# proiect.net
KiCad netlist of a schematic drawn in EAGLE
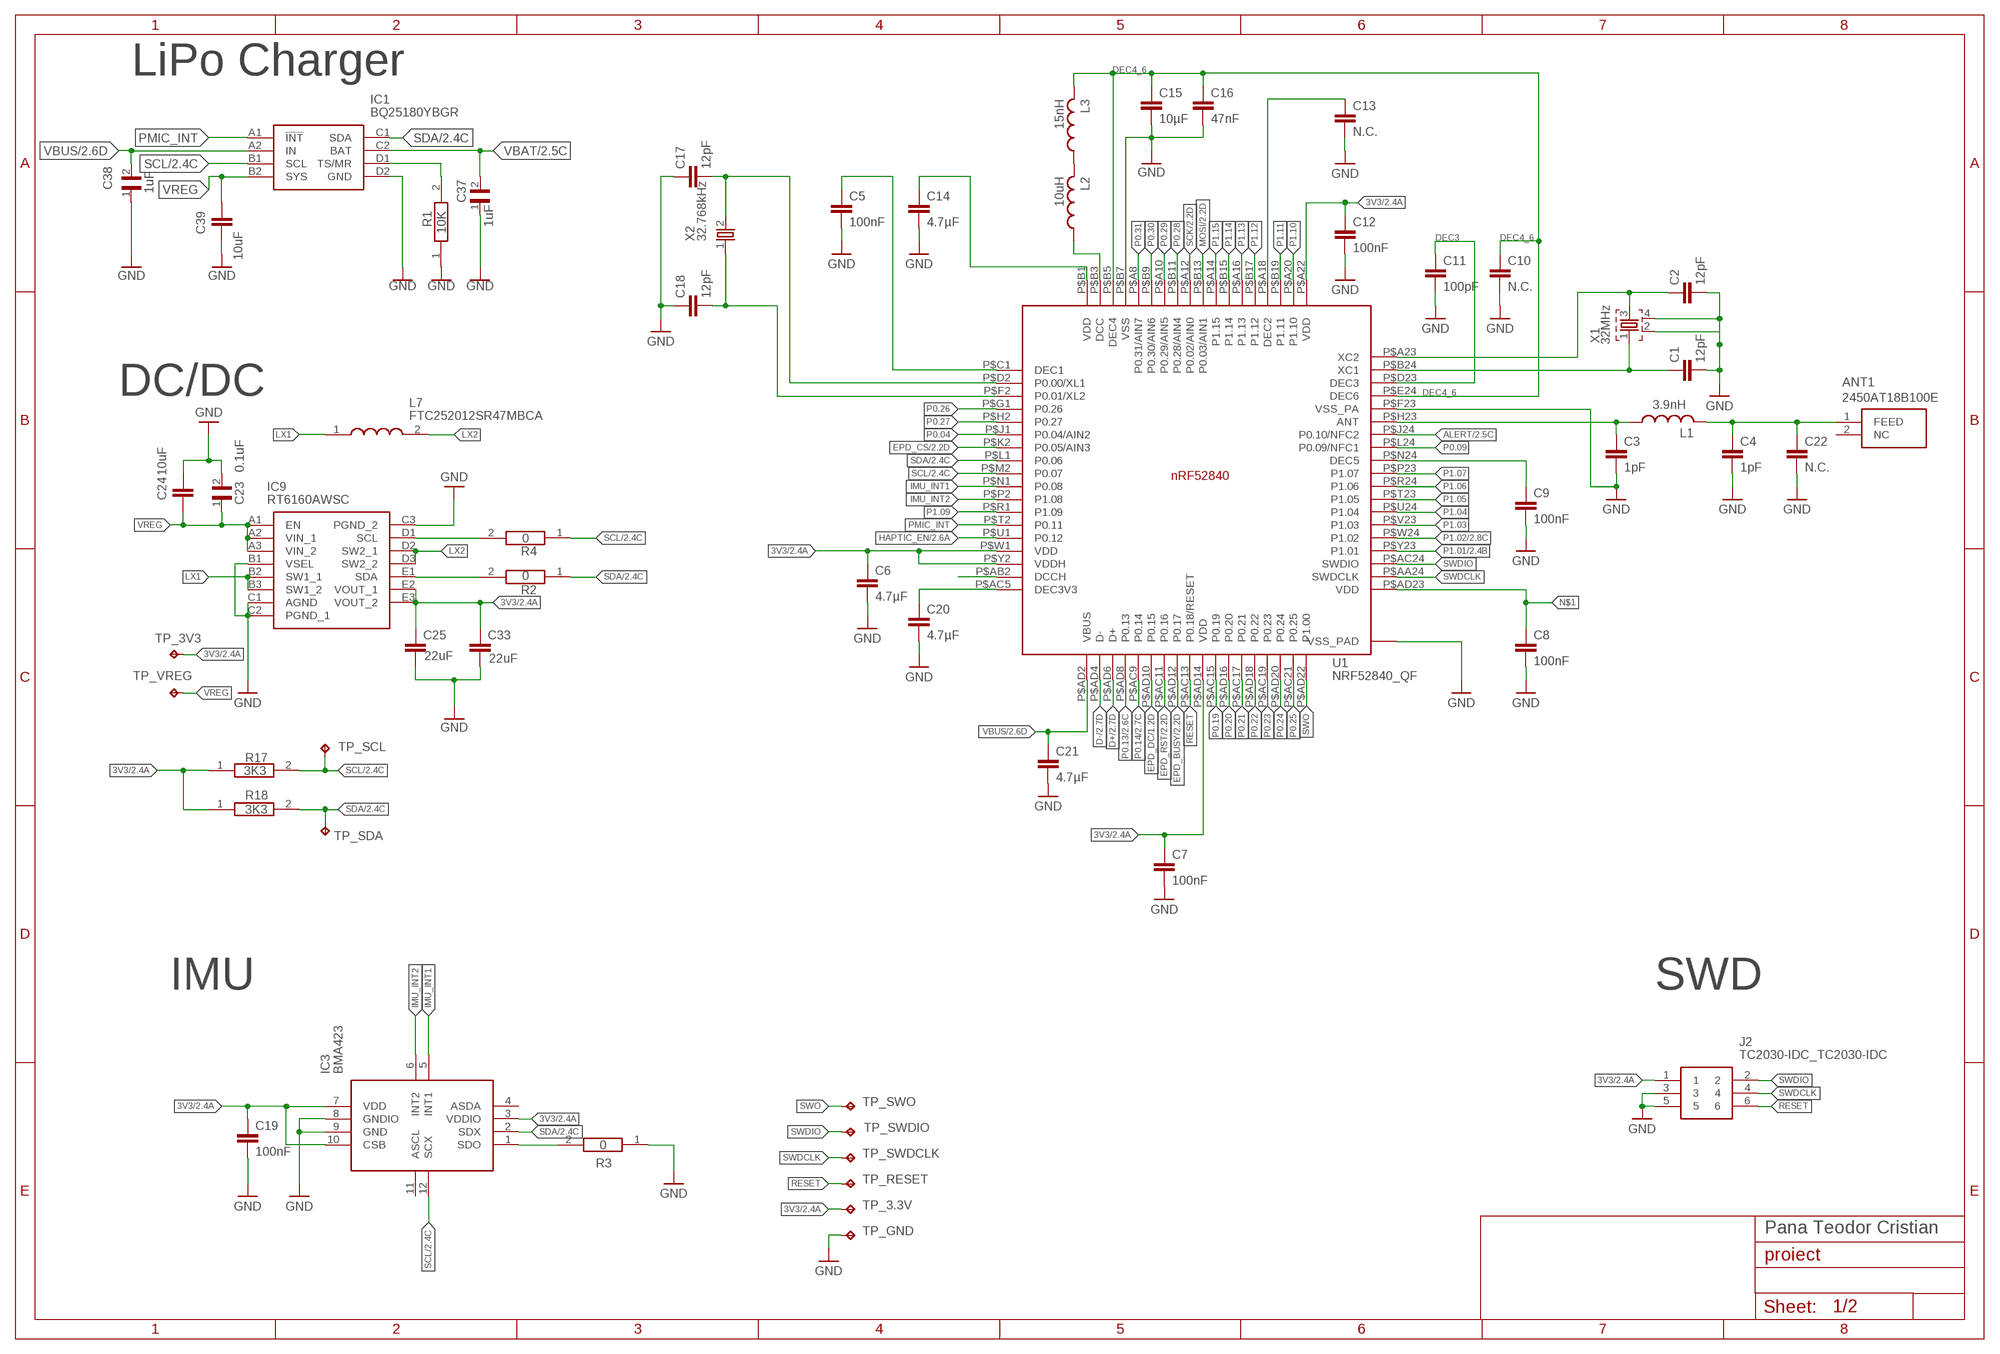
[diagram p0: schematic, sheet 1]
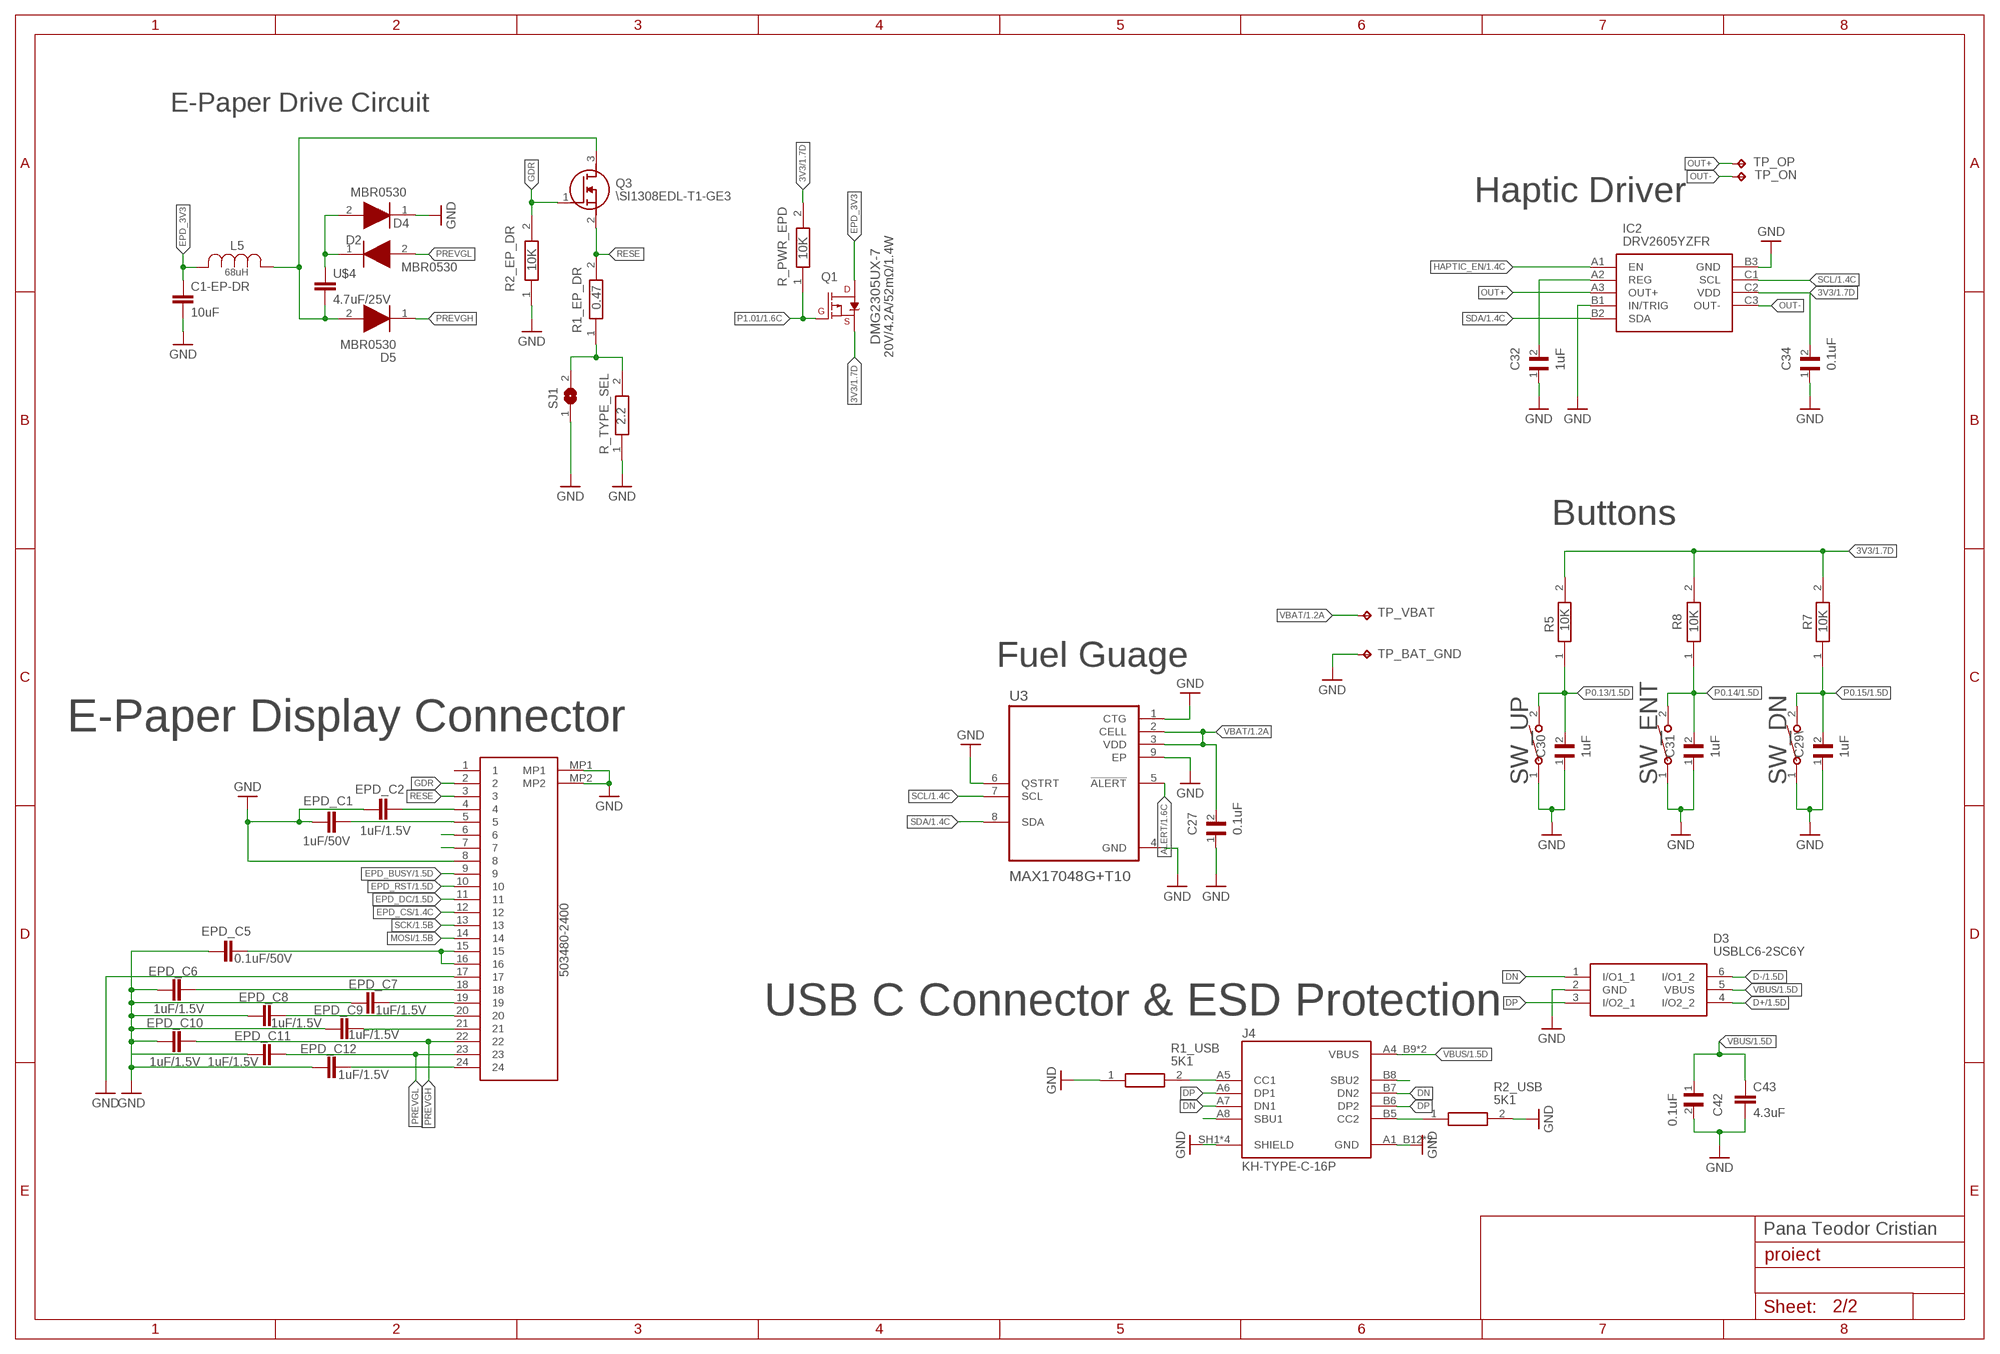
[diagram p1: schematic, sheet 2]

(export (version "E")
  (design (tool "Eeschema 10.0.6"))
  (components
    (comp (ref "C1-EP-DR")
      (value "10uF")
      (footprint "eagle-import:NORDIC_NRF_3_RESC0201_L")
      (libsource (lib "eagle-import") (part "NORDIC_NRF_3_CAPACITOR_0201_L"))
    )
    (comp (ref "C27")
      (value "0.1uF")
      (footprint "eagle-import:GRM011R60J152KE01L_2_CAPC0201X13N")
      (fields (field (name "MF") "Murata") (field (name "MP") "GRM011R60J152KE01L"))
      (libsource (lib "eagle-import") (part "GRM011R60J152KE01L_2_GRM011R60J152KE01L"))
    )
    (comp (ref "C29\\")
      (value "1uF")
      (footprint "eagle-import:GRM011R60J152KE01L_2_CAPC0201X13N")
      (fields (field (name "MF") "Murata") (field (name "MP") "GRM011R60J152KE01L"))
      (libsource (lib "eagle-import") (part "GRM011R60J152KE01L_2_GRM011R60J152KE01L"))
    )
    (comp (ref "C30")
      (value "1uF")
      (footprint "eagle-import:GRM011R60J152KE01L_2_CAPC0201X13N")
      (fields (field (name "MF") "Murata") (field (name "MP") "GRM011R60J152KE01L"))
      (libsource (lib "eagle-import") (part "GRM011R60J152KE01L_2_GRM011R60J152KE01L"))
    )
    (comp (ref "C31")
      (value "1uF")
      (footprint "eagle-import:GRM011R60J152KE01L_2_CAPC0201X13N")
      (fields (field (name "MF") "Murata") (field (name "MP") "GRM011R60J152KE01L"))
      (libsource (lib "eagle-import") (part "GRM011R60J152KE01L_2_GRM011R60J152KE01L"))
    )
    (comp (ref "C32")
      (value "1uF")
      (footprint "eagle-import:GRM011R60J152KE01L_2_CAPC0201X13N")
      (fields (field (name "MF") "Murata") (field (name "MP") "GRM011R60J152KE01L"))
      (libsource (lib "eagle-import") (part "GRM011R60J152KE01L_2_GRM011R60J152KE01L"))
    )
    (comp (ref "C34")
      (value "0.1uF")
      (footprint "eagle-import:GRM011R60J152KE01L_2_CAPC0201X13N")
      (fields (field (name "MF") "Murata") (field (name "MP") "GRM011R60J152KE01L"))
      (libsource (lib "eagle-import") (part "GRM011R60J152KE01L_2_GRM011R60J152KE01L"))
    )
    (comp (ref "C42")
      (value "0.1uF")
      (footprint "eagle-import:GRM011R60J152KE01L_2_CAPC0201X13N")
      (fields (field (name "MF") "Murata") (field (name "MP") "GRM011R60J152KE01L"))
      (libsource (lib "eagle-import") (part "GRM011R60J152KE01L_2_GRM011R60J152KE01L"))
    )
    (comp (ref "C43")
      (value "4.3uF")
      (footprint "eagle-import:NORDIC_NRF_3_RESC0201_L")
      (libsource (lib "eagle-import") (part "NORDIC_NRF_3_CAPACITOR_0201_L"))
    )
    (comp (ref "D2")
      (value "MBR0530")
      (footprint "eagle-import:ESP32_C6_LIBRARY_5_SOD3716X135N")
      (fields (field (name "MF") "ON Semiconductor"))
      (libsource (lib "eagle-import") (part "ESP32_C6_LIBRARY_5_MBR0530"))
    )
    (comp (ref "D3")
      (value "USBLC6-2SC6Y")
      (footprint "eagle-import:ESP32_C6_LIBRARY_3_SOT95P280X145-6N")
      (fields (field (name "MF") "STMicroelectronics"))
      (libsource (lib "eagle-import") (part "ESP32_C6_LIBRARY_3_USBLC6-2SC6Y"))
    )
    (comp (ref "D4")
      (value "MBR0530")
      (footprint "eagle-import:ESP32_C6_LIBRARY_5_SOD3716X135N")
      (fields (field (name "MF") "ON Semiconductor"))
      (libsource (lib "eagle-import") (part "ESP32_C6_LIBRARY_5_MBR0530"))
    )
    (comp (ref "D5")
      (value "MBR0530")
      (footprint "eagle-import:ESP32_C6_LIBRARY_5_SOD3716X135N")
      (fields (field (name "MF") "ON Semiconductor"))
      (libsource (lib "eagle-import") (part "ESP32_C6_LIBRARY_5_MBR0530"))
    )
    (comp (ref "EPD_C1")
      (value "1uF/50V")
      (footprint "eagle-import:PERFECT_0402_0402")
      (libsource (lib "eagle-import") (part "PERFECT_0402_CAP_0402"))
    )
    (comp (ref "EPD_C2")
      (value "1uF/1.5V")
      (footprint "eagle-import:PERFECT_0402_0402")
      (libsource (lib "eagle-import") (part "PERFECT_0402_CAP_0402"))
    )
    (comp (ref "EPD_C5")
      (value "0.1uF/50V")
      (footprint "eagle-import:PERFECT_0402_0402")
      (libsource (lib "eagle-import") (part "PERFECT_0402_CAP_0402"))
    )
    (comp (ref "EPD_C6")
      (value "1uF/1.5V")
      (footprint "eagle-import:PERFECT_0402_0402")
      (libsource (lib "eagle-import") (part "PERFECT_0402_CAP_0402"))
    )
    (comp (ref "EPD_C7")
      (value "1uF/1.5V")
      (footprint "eagle-import:PERFECT_0402_0402")
      (libsource (lib "eagle-import") (part "PERFECT_0402_CAP_0402"))
    )
    (comp (ref "EPD_C8")
      (value "1uF/1.5V")
      (footprint "eagle-import:PERFECT_0402_0402")
      (libsource (lib "eagle-import") (part "PERFECT_0402_CAP_0402"))
    )
    (comp (ref "EPD_C9")
      (value "1uF/1.5V")
      (footprint "eagle-import:PERFECT_0402_0402")
      (libsource (lib "eagle-import") (part "PERFECT_0402_CAP_0402"))
    )
    (comp (ref "EPD_C10")
      (value "1uF/1.5V")
      (footprint "eagle-import:PERFECT_0402_0402")
      (libsource (lib "eagle-import") (part "PERFECT_0402_CAP_0402"))
    )
    (comp (ref "EPD_C11")
      (value "1uF/1.5V")
      (footprint "eagle-import:PERFECT_0402_0402")
      (libsource (lib "eagle-import") (part "PERFECT_0402_CAP_0402"))
    )
    (comp (ref "EPD_C12")
      (value "1uF/1.5V")
      (footprint "eagle-import:PERFECT_0402_0402")
      (libsource (lib "eagle-import") (part "PERFECT_0402_CAP_0402"))
    )
    (comp (ref "IC2")
      (value "DRV2605YZFR")
      (footprint "eagle-import:DRV2605YZFR_BGA9C50P3X3_144X144X62")
      (libsource (lib "eagle-import") (part "DRV2605YZFR_DRV2605YZFR"))
    )
    (comp (ref "J1")
      (value "503480-2400")
      (footprint "eagle-import:503480-2400_5034802400")
      (fields (field (name "MOUSER_PART_NUMBER") "538-503480-2400"))
      (libsource (lib "eagle-import") (part "503480-2400_503480-2400"))
    )
    (comp (ref "J4")
      (value "KH-TYPE-C-16P")
      (footprint "eagle-import:KH-TYPE-C-16P_KINGHELM_KH-TYPE-C-16P")
      (fields (field (name "MF") "kinghelm"))
      (libsource (lib "eagle-import") (part "KH-TYPE-C-16P_KH-TYPE-C-16P"))
    )
    (comp (ref "L5")
      (value "68uH")
      (footprint "eagle-import:ESP32_C6_LIBRARY_2_IND_4828-WE-TPC_WRE")
      (fields
        (field (name "MANUFACTURER_PART_NUMBER") "744043680")
        (field (name "COPYRIGHT") "Copyright (C) 2024 Ultra Librarian. All rights reserved.")
      )
      (libsource (lib "eagle-import") (part "ESP32_C6_LIBRARY_2_744043680IND_4828-WE-TPC_WRE"))
    )
    (comp (ref "Q1")
      (value "20V/4.2A/52mΩ/1.4W")
      (footprint "eagle-import:ESP32_C6_LIBRARY_4_ESP32_C6_LIBRARY_4_ESP32_C6_LIBRARY_4_ESP32_C6_LIBRARY_4_ESP32_WROVER_SPARKFUN-DISCRETESEMI_SOT23-3")
      (libsource (lib "eagle-import") (part "ESP32_C6_LIBRARY_4_ESP32_WROVER_SPARKFUN-DISCRETESEMI_MOSFET_PCH-DMG2305UX-7"))
    )
    (comp (ref "Q3")
      (value "\\SI1308EDL-T1-GE3")
      (footprint "eagle-import:ESP32_C6_LIBRARY_6_SOT65P210X110-3N")
      (fields (field (name "MF") "Vishay Siliconix") (field (name "MP") "SI1308EDL-T1-GE3"))
      (libsource (lib "eagle-import") (part "ESP32_C6_LIBRARY_6_SI1308EDL-T1-GE3"))
    )
    (comp (ref "R1_EP_DR")
      (value "0.47")
      (footprint "eagle-import:CPF0201D7K68C1_0201")
      (libsource (lib "eagle-import") (part "CPF0201D7K68C1_CPF0201D7K68C1"))
    )
    (comp (ref "R1_USB")
      (value "5K1")
      (footprint "eagle-import:CPF0201D7K68C1_0201")
      (libsource (lib "eagle-import") (part "CPF0201D7K68C1_CPF0201D7K68C1"))
    )
    (comp (ref "R2_EP_DR")
      (value "10K")
      (footprint "eagle-import:CPF0201D7K68C1_0201")
      (libsource (lib "eagle-import") (part "CPF0201D7K68C1_CPF0201D7K68C1"))
    )
    (comp (ref "R2_USB")
      (value "5K1")
      (footprint "eagle-import:CPF0201D7K68C1_0201")
      (libsource (lib "eagle-import") (part "CPF0201D7K68C1_CPF0201D7K68C1"))
    )
    (comp (ref "R5")
      (value "10K")
      (footprint "eagle-import:CPF0201D7K68C1_0201")
      (libsource (lib "eagle-import") (part "CPF0201D7K68C1_CPF0201D7K68C1"))
    )
    (comp (ref "R7")
      (value "10K")
      (footprint "eagle-import:CPF0201D7K68C1_0201")
      (libsource (lib "eagle-import") (part "CPF0201D7K68C1_CPF0201D7K68C1"))
    )
    (comp (ref "R8")
      (value "10K")
      (footprint "eagle-import:CPF0201D7K68C1_0201")
      (libsource (lib "eagle-import") (part "CPF0201D7K68C1_CPF0201D7K68C1"))
    )
    (comp (ref "R_PWR_EPD")
      (value "10K")
      (footprint "eagle-import:CPF0201D7K68C1_0201")
      (libsource (lib "eagle-import") (part "CPF0201D7K68C1_CPF0201D7K68C1"))
    )
    (comp (ref "R_TYPE_SEL")
      (value "2.2")
      (footprint "eagle-import:CPF0201D7K68C1_0201")
      (libsource (lib "eagle-import") (part "CPF0201D7K68C1_CPF0201D7K68C1"))
    )
    (comp (ref "SJ1")
      (value "ESP32_C6_LIBRARY_7_JUMPER_SJ")
      (footprint "eagle-import:ESP32_C6_LIBRARY_7_JUMPER_SJ")
      (libsource (lib "eagle-import") (part "ESP32_C6_LIBRARY_7_JUMPER_SJ"))
    )
    (comp (ref "SW_DN")
      (value "2025-10-22_07-23-44_LIBRARY_EVP-AKE31ASW_EVP-AKE31A_PAN")
      (footprint "eagle-import:2025-10-22_07-23-44_LIBRARY_SW_EVP-AKE31A_PAN")
      (fields
        (field (name "MANUFACTURER_PART_NUMBER") "EVP-AKE31A")
        (field (name "COPYRIGHT") "Copyright (C) 2025 Ultra Librarian. All rights reserved.")
      )
      (libsource (lib "eagle-import") (part "2025-10-22_07-23-44_LIBRARY_EVP-AKE31ASW_EVP-AKE31A_PAN"))
    )
    (comp (ref "SW_ENT")
      (value "2025-10-22_07-23-44_LIBRARY_EVP-AKE31ASW_EVP-AKE31A_PAN")
      (footprint "eagle-import:2025-10-22_07-23-44_LIBRARY_SW_EVP-AKE31A_PAN")
      (fields
        (field (name "MANUFACTURER_PART_NUMBER") "EVP-AKE31A")
        (field (name "COPYRIGHT") "Copyright (C) 2025 Ultra Librarian. All rights reserved.")
      )
      (libsource (lib "eagle-import") (part "2025-10-22_07-23-44_LIBRARY_EVP-AKE31ASW_EVP-AKE31A_PAN"))
    )
    (comp (ref "SW_UP")
      (value "2025-10-22_07-23-44_LIBRARY_EVP-AKE31ASW_EVP-AKE31A_PAN")
      (footprint "eagle-import:2025-10-22_07-23-44_LIBRARY_SW_EVP-AKE31A_PAN")
      (fields
        (field (name "MANUFACTURER_PART_NUMBER") "EVP-AKE31A")
        (field (name "COPYRIGHT") "Copyright (C) 2025 Ultra Librarian. All rights reserved.")
      )
      (libsource (lib "eagle-import") (part "2025-10-22_07-23-44_LIBRARY_EVP-AKE31ASW_EVP-AKE31A_PAN"))
    )
    (comp (ref "TP_BAT_GND")
      (value "HECTOR_WATCH_1_TPTP20R")
      (footprint "eagle-import:HECTOR_WATCH_1_TP20R")
      (libsource (lib "eagle-import") (part "HECTOR_WATCH_1_TPTP20R"))
    )
    (comp (ref "TP_ON")
      (value "HECTOR_WATCH_1_TPTP20R")
      (footprint "eagle-import:HECTOR_WATCH_1_TP20R")
      (libsource (lib "eagle-import") (part "HECTOR_WATCH_1_TPTP20R"))
    )
    (comp (ref "TP_OP")
      (value "HECTOR_WATCH_1_TPTP20R")
      (footprint "eagle-import:HECTOR_WATCH_1_TP20R")
      (libsource (lib "eagle-import") (part "HECTOR_WATCH_1_TPTP20R"))
    )
    (comp (ref "TP_VBAT")
      (value "HECTOR_WATCH_1_TPTP20R")
      (footprint "eagle-import:HECTOR_WATCH_1_TP20R")
      (libsource (lib "eagle-import") (part "HECTOR_WATCH_1_TPTP20R"))
    )
    (comp (ref "U$4")
      (value "4.7uF/25V")
      (footprint "eagle-import:NORDIC_NRF_3_RESC0201_L")
      (libsource (lib "eagle-import") (part "NORDIC_NRF_3_CAPACITOR_0201_L"))
    )
    (comp (ref "U3")
      (value "MAX17048G+T10")
      (footprint "eagle-import:ESP32_C6_LIBRARY_SON50P200X200X80-9N")
      (fields (field (name "MF") "Analog Devices"))
      (libsource (lib "eagle-import") (part "ESP32_C6_LIBRARY_MAX17048G+T10"))
    )
    (comp (ref "ANT1")
      (value "2450AT18B100E")
      (footprint "eagle-import:2450AT18B100E_ANTC3216X140N")
      (fields (field (name "MOUSER_PART_NUMBER") "609-2450AT18B100E"))
      (libsource (lib "eagle-import") (part "2450AT18B100E_2450AT18B100E"))
    )
    (comp (ref "C1")
      (value "12pF")
      (footprint "eagle-import:PERFECT_0402_0402")
      (libsource (lib "eagle-import") (part "PERFECT_0402_CAP_0402"))
    )
    (comp (ref "C2")
      (value "12pF")
      (footprint "eagle-import:PERFECT_0402_0402")
      (libsource (lib "eagle-import") (part "PERFECT_0402_CAP_0402"))
    )
    (comp (ref "C3")
      (value "1pF")
      (footprint "eagle-import:NORDIC_NRF_3_RESC0201_L")
      (libsource (lib "eagle-import") (part "NORDIC_NRF_3_CAPACITOR_0201_L"))
    )
    (comp (ref "C4")
      (value "1pF")
      (footprint "eagle-import:NORDIC_NRF_3_RESC0201_L")
      (libsource (lib "eagle-import") (part "NORDIC_NRF_3_CAPACITOR_0201_L"))
    )
    (comp (ref "C5")
      (value "100nF")
      (footprint "eagle-import:NORDIC_NRF_3_RESC0201_L")
      (libsource (lib "eagle-import") (part "NORDIC_NRF_3_CAPACITOR_0201_L"))
    )
    (comp (ref "C6")
      (value "4.7µF")
      (footprint "eagle-import:PERFECT_0402_0402")
      (libsource (lib "eagle-import") (part "PERFECT_0402_CAP_0402"))
    )
    (comp (ref "C7")
      (value "100nF")
      (footprint "eagle-import:NORDIC_NRF_3_RESC0201_L")
      (libsource (lib "eagle-import") (part "NORDIC_NRF_3_CAPACITOR_0201_L"))
    )
    (comp (ref "C8")
      (value "100nF")
      (footprint "eagle-import:NORDIC_NRF_3_RESC0201_L")
      (libsource (lib "eagle-import") (part "NORDIC_NRF_3_CAPACITOR_0201_L"))
    )
    (comp (ref "C9")
      (value "100nF")
      (footprint "eagle-import:NORDIC_NRF_3_RESC0201_L")
      (libsource (lib "eagle-import") (part "NORDIC_NRF_3_CAPACITOR_0201_L"))
    )
    (comp (ref "C10")
      (value "N.C.")
      (footprint "eagle-import:PERFECT_0402_0402")
      (libsource (lib "eagle-import") (part "PERFECT_0402_CAP_0402"))
    )
    (comp (ref "C11")
      (value "100pF")
      (footprint "eagle-import:PERFECT_0402_0402")
      (libsource (lib "eagle-import") (part "PERFECT_0402_CAP_0402"))
    )
    (comp (ref "C12")
      (value "100nF")
      (footprint "eagle-import:PERFECT_0402_0402")
      (libsource (lib "eagle-import") (part "PERFECT_0402_CAP_0402"))
    )
    (comp (ref "C13")
      (value "N.C.")
      (footprint "eagle-import:PERFECT_0402_0402")
      (libsource (lib "eagle-import") (part "PERFECT_0402_CAP_0402"))
    )
    (comp (ref "C14")
      (value "4.7µF")
      (footprint "eagle-import:PERFECT_0402_0402")
      (libsource (lib "eagle-import") (part "PERFECT_0402_CAP_0402"))
    )
    (comp (ref "C15")
      (value "10µF")
      (footprint "eagle-import:PERFECT_0402_0402")
      (libsource (lib "eagle-import") (part "PERFECT_0402_CAP_0402"))
    )
    (comp (ref "C16")
      (value "47nF")
      (footprint "eagle-import:PERFECT_0402_0402")
      (libsource (lib "eagle-import") (part "PERFECT_0402_CAP_0402"))
    )
    (comp (ref "C17")
      (value "12pF")
      (footprint "eagle-import:PERFECT_0402_0402")
      (libsource (lib "eagle-import") (part "PERFECT_0402_CAP_0402"))
    )
    (comp (ref "C18")
      (value "12pF")
      (footprint "eagle-import:PERFECT_0402_0402")
      (libsource (lib "eagle-import") (part "PERFECT_0402_CAP_0402"))
    )
    (comp (ref "C19")
      (value "100nF")
      (footprint "eagle-import:PERFECT_0402_0402")
      (libsource (lib "eagle-import") (part "PERFECT_0402_CAP_0402"))
    )
    (comp (ref "C20")
      (value "4.7µF")
      (footprint "eagle-import:PERFECT_0402_0402")
      (libsource (lib "eagle-import") (part "PERFECT_0402_CAP_0402"))
    )
    (comp (ref "C21")
      (value "4.7µF")
      (footprint "eagle-import:NORDIC_NRF_3_RESC0201_L")
      (libsource (lib "eagle-import") (part "NORDIC_NRF_3_CAPACITOR_0201_L"))
    )
    (comp (ref "C22")
      (value "N.C.")
      (footprint "eagle-import:NORDIC_NRF_3_RESC0201_L")
      (libsource (lib "eagle-import") (part "NORDIC_NRF_3_CAPACITOR_0201_L"))
    )
    (comp (ref "C23")
      (value "0.1uF")
      (footprint "eagle-import:GRM011R60J152KE01L_2_CAPC0201X13N")
      (fields (field (name "MF") "Murata") (field (name "MP") "GRM011R60J152KE01L"))
      (libsource (lib "eagle-import") (part "GRM011R60J152KE01L_2_GRM011R60J152KE01L"))
    )
    (comp (ref "C24")
      (value "10uF")
      (footprint "eagle-import:PERFECT_0402_0402")
      (libsource (lib "eagle-import") (part "PERFECT_0402_CAP_0402"))
    )
    (comp (ref "C25")
      (value "22uF")
      (footprint "eagle-import:PERFECT_0402_0402")
      (libsource (lib "eagle-import") (part "PERFECT_0402_CAP_0402"))
    )
    (comp (ref "C33")
      (value "22uF")
      (footprint "eagle-import:PERFECT_0402_0402")
      (libsource (lib "eagle-import") (part "PERFECT_0402_CAP_0402"))
    )
    (comp (ref "C37")
      (value "1uF")
      (footprint "eagle-import:GRM011R60J152KE01L_2_CAPC0201X13N")
      (fields (field (name "MF") "Murata") (field (name "MP") "GRM011R60J152KE01L"))
      (libsource (lib "eagle-import") (part "GRM011R60J152KE01L_2_GRM011R60J152KE01L"))
    )
    (comp (ref "C38")
      (value "1uF")
      (footprint "eagle-import:GRM011R60J152KE01L_1_0201")
      (libsource (lib "eagle-import") (part "GRM011R60J152KE01L_1_GRM011R60J152KE01L"))
    )
    (comp (ref "C39")
      (value "10uF")
      (footprint "eagle-import:NORDIC_NRF_3_RESC0201_L")
      (libsource (lib "eagle-import") (part "NORDIC_NRF_3_CAPACITOR_0201_L"))
    )
    (comp (ref "IC1")
      (value "BQ25180YBGR")
      (footprint "eagle-import:BQ25180YBGR_BGA8C40P2X4_100X155X50")
      (fields (field (name "MOUSER_PART_NUMBER") "595-BQ25180YBGR"))
      (libsource (lib "eagle-import") (part "BQ25180YBGR_BQ25180YBGR"))
    )
    (comp (ref "IC3")
      (value "BMA423")
      (footprint "eagle-import:BMA423_BMA423")
      (fields (field (name "MOUSER_PART_NUMBER") "262-BMA423"))
      (libsource (lib "eagle-import") (part "BMA423_BMA423"))
    )
    (comp (ref "IC9")
      (value "RT6160AWSC")
      (footprint "eagle-import:RT6160AWSC_BGA15C40P3X5_140X230X60")
      (fields (field (name "MOUSER_PART_NUMBER") "835-RT6160AWSC"))
      (libsource (lib "eagle-import") (part "RT6160AWSC_RT6160AWSC"))
    )
    (comp (ref "J2")
      (value "TC2030-IDC_TC2030-IDC")
      (footprint "eagle-import:TC2030-IDC_TC2030IDC")
      (fields (field (name "MANUFACTURER_PART_NUMBER") "TC2030-IDC"))
      (libsource (lib "eagle-import") (part "TC2030-IDC_TC2030-IDC"))
    )
    (comp (ref "L1")
      (value "3.9nH")
      (footprint "eagle-import:NORDIC_NRF_2_RESC0402_L")
      (libsource (lib "eagle-import") (part "NORDIC_NRF_2_INDUCTOR_0402_L"))
    )
    (comp (ref "L2")
      (value "10uH")
      (footprint "eagle-import:NORDIC_NRF_2_RESC0402_L")
      (libsource (lib "eagle-import") (part "NORDIC_NRF_2_INDUCTOR_0402_L"))
    )
    (comp (ref "L3")
      (value "15nH")
      (footprint "eagle-import:NORDIC_NRF_2_RESC0402_L")
      (libsource (lib "eagle-import") (part "NORDIC_NRF_2_INDUCTOR_0402_L"))
    )
    (comp (ref "L7")
      (value "FTC252012SR47MBCA")
      (footprint "eagle-import:MLP2016SR47MT0S1_INDC2016X100N")
      (libsource (lib "eagle-import") (part "MLP2016SR47MT0S1_FTC252012SR47MBCA"))
    )
    (comp (ref "R1")
      (value "10K")
      (footprint "eagle-import:CPF0201D7K68C1_0201")
      (libsource (lib "eagle-import") (part "CPF0201D7K68C1_CPF0201D7K68C1"))
    )
    (comp (ref "R2")
      (value "0")
      (footprint "eagle-import:CPF0201D7K68C1_0201")
      (libsource (lib "eagle-import") (part "CPF0201D7K68C1_CPF0201D7K68C1"))
    )
    (comp (ref "R3")
      (value "0")
      (footprint "eagle-import:CPF0201D7K68C1_0201")
      (libsource (lib "eagle-import") (part "CPF0201D7K68C1_CPF0201D7K68C1"))
    )
    (comp (ref "R4")
      (value "0")
      (footprint "eagle-import:CPF0201D7K68C1_0201")
      (libsource (lib "eagle-import") (part "CPF0201D7K68C1_CPF0201D7K68C1"))
    )
    (comp (ref "R17")
      (value "3K3")
      (footprint "eagle-import:CPF0201D7K68C1_0201")
      (libsource (lib "eagle-import") (part "CPF0201D7K68C1_CPF0201D7K68C1"))
    )
    (comp (ref "R18")
      (value "3K3")
      (footprint "eagle-import:CPF0201D7K68C1_0201")
      (libsource (lib "eagle-import") (part "CPF0201D7K68C1_CPF0201D7K68C1"))
    )
    (comp (ref "TP_3.3V")
      (value "HECTOR_WATCH_1_TPTP20R")
      (footprint "eagle-import:HECTOR_WATCH_1_TP20R")
      (libsource (lib "eagle-import") (part "HECTOR_WATCH_1_TPTP20R"))
    )
    (comp (ref "TP_3V3")
      (value "HECTOR_WATCH_1_TPTP20R")
      (footprint "eagle-import:HECTOR_WATCH_1_TP20R")
      (libsource (lib "eagle-import") (part "HECTOR_WATCH_1_TPTP20R"))
    )
    (comp (ref "TP_GND")
      (value "HECTOR_WATCH_1_TPTP20R")
      (footprint "eagle-import:HECTOR_WATCH_1_TP20R")
      (libsource (lib "eagle-import") (part "HECTOR_WATCH_1_TPTP20R"))
    )
    (comp (ref "TP_RESET")
      (value "HECTOR_WATCH_1_TPTP20R")
      (footprint "eagle-import:HECTOR_WATCH_1_TP20R")
      (libsource (lib "eagle-import") (part "HECTOR_WATCH_1_TPTP20R"))
    )
    (comp (ref "TP_SCL")
      (value "HECTOR_WATCH_1_TPTP20R")
      (footprint "eagle-import:HECTOR_WATCH_1_TP20R")
      (libsource (lib "eagle-import") (part "HECTOR_WATCH_1_TPTP20R"))
    )
    (comp (ref "TP_SDA")
      (value "HECTOR_WATCH_1_TPTP20R")
      (footprint "eagle-import:HECTOR_WATCH_1_TP20R")
      (libsource (lib "eagle-import") (part "HECTOR_WATCH_1_TPTP20R"))
    )
    (comp (ref "TP_SWDCLK")
      (value "HECTOR_WATCH_1_TPTP20R")
      (footprint "eagle-import:HECTOR_WATCH_1_TP20R")
      (libsource (lib "eagle-import") (part "HECTOR_WATCH_1_TPTP20R"))
    )
    (comp (ref "TP_SWDIO")
      (value "HECTOR_WATCH_1_TPTP20R")
      (footprint "eagle-import:HECTOR_WATCH_1_TP20R")
      (libsource (lib "eagle-import") (part "HECTOR_WATCH_1_TPTP20R"))
    )
    (comp (ref "TP_SWO")
      (value "HECTOR_WATCH_1_TPTP20R")
      (footprint "eagle-import:HECTOR_WATCH_1_TP20R")
      (libsource (lib "eagle-import") (part "HECTOR_WATCH_1_TPTP20R"))
    )
    (comp (ref "TP_VREG")
      (value "HECTOR_WATCH_1_TPTP20R")
      (footprint "eagle-import:HECTOR_WATCH_1_TP20R")
      (libsource (lib "eagle-import") (part "HECTOR_WATCH_1_TPTP20R"))
    )
    (comp (ref "U1")
      (value "NRF52840_QF")
      (footprint "eagle-import:NORDIC_NRF_4_AQFN50P700X700X85_HS-74N")
      (libsource (lib "eagle-import") (part "NORDIC_NRF_4_NRF52840_QF"))
    )
    (comp (ref "X1")
      (value "32MHz")
      (footprint "eagle-import:NORDIC_NRF_BT-XTAL_2016_N")
      (libsource (lib "eagle-import") (part "NORDIC_NRF_XTAL_32MHZ"))
    )
    (comp (ref "X2")
      (value "32.768kHz")
      (footprint "eagle-import:NORDIC_NRF_1_XTAL_3215_N")
      (libsource (lib "eagle-import") (part "NORDIC_NRF_1_XTAL_32KHZ"))
    )
  )
  (nets
    (net (code "1") (name "3V3{slash}1.7D") (class "Default")
      (node (ref "C34") (pin "2") (pinfunction "2_2") (pintype "passive"))
      (node (ref "IC2") (pin "C2") (pinfunction "VDD_C2") (pintype "bidirectional"))
      (node (ref "Q1") (pin "2") (pinfunction "S_2") (pintype "bidirectional"))
      (node (ref "R5") (pin "2") (pinfunction "2_2") (pintype "bidirectional"))
      (node (ref "R7") (pin "2") (pinfunction "2_2") (pintype "bidirectional"))
      (node (ref "R8") (pin "2") (pinfunction "2_2") (pintype "bidirectional"))
      (node (ref "R_PWR_EPD") (pin "2") (pinfunction "2_2") (pintype "bidirectional"))
    )
    (net (code "2") (name "3V3{slash}2.4A") (class "Default")
      (node (ref "C12") (pin "1") (pinfunction "1_1") (pintype "passive"))
      (node (ref "C19") (pin "1") (pinfunction "1_1") (pintype "passive"))
      (node (ref "C25") (pin "1") (pinfunction "1_1") (pintype "passive"))
      (node (ref "C33") (pin "1") (pinfunction "1_1") (pintype "passive"))
      (node (ref "C6") (pin "1") (pinfunction "1_1") (pintype "passive"))
      (node (ref "C7") (pin "1") (pinfunction "1_1") (pintype "passive"))
      (node (ref "IC3") (pin "10") (pinfunction "CSB_10") (pintype "bidirectional"))
      (node (ref "IC3") (pin "3") (pinfunction "VDDIO_3") (pintype "bidirectional"))
      (node (ref "IC3") (pin "7") (pinfunction "VDD_7") (pintype "bidirectional"))
      (node (ref "IC9") (pin "E2") (pinfunction "VOUT_1_E2") (pintype "bidirectional"))
      (node (ref "IC9") (pin "E3") (pinfunction "VOUT_2_E3") (pintype "bidirectional"))
      (node (ref "J2") (pin "1") (pinfunction "1_1") (pintype "bidirectional"))
      (node (ref "R17") (pin "1") (pinfunction "1_1") (pintype "bidirectional"))
      (node (ref "R18") (pin "1") (pinfunction "1_1") (pintype "bidirectional"))
      (node (ref "TP_3.3V") (pin "TP") (pinfunction "TP_TP") (pintype "input"))
      (node (ref "TP_3V3") (pin "TP") (pinfunction "TP_TP") (pintype "input"))
      (node (ref "U1") (pin "P$A22") (pinfunction "VDD_P$A22") (pintype "power_in"))
      (node (ref "U1") (pin "P$AD14") (pinfunction "VDD_P$AD14") (pintype "power_in"))
      (node (ref "U1") (pin "P$W1") (pinfunction "VDD_P$W1") (pintype "power_in"))
      (node (ref "U1") (pin "P$Y2") (pinfunction "VDDH_P$Y2") (pintype "power_in"))
    )
    (net (code "3") (name "ALERT{slash}1.6C") (class "Default")
      (node (ref "U3") (pin "5") (pinfunction "~{ALERT}_5") (pintype "output"))
    )
    (net (code "4") (name "ALERT{slash}2.5C") (class "Default")
      (node (ref "U1") (pin "P$J24") (pinfunction "P0.10/NFC2_P$J24") (pintype "bidirectional"))
    )
    (net (code "5") (name "D+{slash}1.5D") (class "Default")
      (node (ref "D3") (pin "4") (pinfunction "I/O2_2_4") (pintype "bidirectional"))
    )
    (net (code "6") (name "D+{slash}2.7D") (class "Default")
      (node (ref "U1") (pin "P$AD6") (pinfunction "D+_P$AD6") (pintype "bidirectional"))
    )
    (net (code "7") (name "D-{slash}1.5D") (class "Default")
      (node (ref "D3") (pin "6") (pinfunction "I/O1_2_6") (pintype "bidirectional"))
    )
    (net (code "8") (name "D-{slash}2.7D") (class "Default")
      (node (ref "U1") (pin "P$AD4") (pinfunction "D-_P$AD4") (pintype "bidirectional"))
    )
    (net (code "9") (name "DN") (class "Default")
      (node (ref "D3") (pin "1") (pinfunction "I/O1_1_1") (pintype "bidirectional"))
      (node (ref "J4") (pin "A7") (pinfunction "DN1_A7") (pintype "bidirectional"))
      (node (ref "J4") (pin "B7") (pinfunction "DN2_B7") (pintype "bidirectional"))
    )
    (net (code "10") (name "DP") (class "Default")
      (node (ref "D3") (pin "3") (pinfunction "I/O2_1_3") (pintype "bidirectional"))
      (node (ref "J4") (pin "A6") (pinfunction "DP1_A6") (pintype "bidirectional"))
      (node (ref "J4") (pin "B6") (pinfunction "DP2_B6") (pintype "bidirectional"))
    )
    (net (code "11") (name "EPD_3V3") (class "Default")
      (node (ref "C1-EP-DR") (pin "1") (pinfunction "1_1") (pintype "passive"))
      (node (ref "L5") (pin "2") (pinfunction "2_2") (pintype "passive"))
      (node (ref "Q1") (pin "3") (pinfunction "D_3") (pintype "bidirectional"))
    )
    (net (code "12") (name "EPD_BUSY{slash}1.5D") (class "Default")
      (node (ref "J1") (pin "9") (pinfunction "9_9") (pintype "bidirectional"))
    )
    (net (code "13") (name "EPD_BUSY{slash}2.2D") (class "Default")
      (node (ref "U1") (pin "P$AD12") (pinfunction "P0.17_P$AD12") (pintype "bidirectional"))
    )
    (net (code "14") (name "EPD_CS{slash}1.4C") (class "Default")
      (node (ref "J1") (pin "12") (pinfunction "12_12") (pintype "bidirectional"))
    )
    (net (code "15") (name "EPD_CS{slash}2.2D") (class "Default")
      (node (ref "U1") (pin "P$K2") (pinfunction "P0.05/AIN3_P$K2") (pintype "bidirectional"))
    )
    (net (code "16") (name "EPD_DC{slash}1.2D") (class "Default")
      (node (ref "U1") (pin "P$AD10") (pinfunction "P0.15_P$AD10") (pintype "bidirectional"))
    )
    (net (code "17") (name "EPD_DC{slash}1.5D") (class "Default")
      (node (ref "J1") (pin "11") (pinfunction "11_11") (pintype "bidirectional"))
    )
    (net (code "18") (name "EPD_RST{slash}1.5D") (class "Default")
      (node (ref "J1") (pin "10") (pinfunction "10_10") (pintype "bidirectional"))
    )
    (net (code "19") (name "EPD_RST{slash}2.2D") (class "Default")
      (node (ref "U1") (pin "P$AC11") (pinfunction "P0.16_P$AC11") (pintype "bidirectional"))
    )
    (net (code "20") (name "GDR") (class "Default")
      (node (ref "J1") (pin "2") (pinfunction "2_2") (pintype "bidirectional"))
      (node (ref "Q3") (pin "1") (pinfunction "G_1") (pintype "bidirectional"))
      (node (ref "R2_EP_DR") (pin "2") (pinfunction "2_2") (pintype "bidirectional"))
    )
    (net (code "21") (name "GND") (class "Default")
      (node (ref "C1") (pin "2") (pinfunction "2_2") (pintype "passive"))
      (node (ref "C1-EP-DR") (pin "2") (pinfunction "2_2") (pintype "passive"))
      (node (ref "C10") (pin "2") (pinfunction "2_2") (pintype "passive"))
      (node (ref "C11") (pin "2") (pinfunction "2_2") (pintype "passive"))
      (node (ref "C12") (pin "2") (pinfunction "2_2") (pintype "passive"))
      (node (ref "C13") (pin "2") (pinfunction "2_2") (pintype "passive"))
      (node (ref "C14") (pin "2") (pinfunction "2_2") (pintype "passive"))
      (node (ref "C15") (pin "2") (pinfunction "2_2") (pintype "passive"))
      (node (ref "C16") (pin "2") (pinfunction "2_2") (pintype "passive"))
      (node (ref "C17") (pin "1") (pinfunction "1_1") (pintype "passive"))
      (node (ref "C18") (pin "1") (pinfunction "1_1") (pintype "passive"))
      (node (ref "C19") (pin "2") (pinfunction "2_2") (pintype "passive"))
      (node (ref "C2") (pin "2") (pinfunction "2_2") (pintype "passive"))
      (node (ref "C20") (pin "2") (pinfunction "2_2") (pintype "passive"))
      (node (ref "C21") (pin "2") (pinfunction "2_2") (pintype "passive"))
      (node (ref "C22") (pin "2") (pinfunction "2_2") (pintype "passive"))
      (node (ref "C23") (pin "2") (pinfunction "2_2") (pintype "passive"))
      (node (ref "C24") (pin "1") (pinfunction "1_1") (pintype "passive"))
      (node (ref "C25") (pin "2") (pinfunction "2_2") (pintype "passive"))
      (node (ref "C27") (pin "1") (pinfunction "1_1") (pintype "passive"))
      (node (ref "C29\\") (pin "1") (pinfunction "1_1") (pintype "passive"))
      (node (ref "C3") (pin "2") (pinfunction "2_2") (pintype "passive"))
      (node (ref "C30") (pin "1") (pinfunction "1_1") (pintype "passive"))
      (node (ref "C31") (pin "1") (pinfunction "1_1") (pintype "passive"))
      (node (ref "C32") (pin "1") (pinfunction "1_1") (pintype "passive"))
      (node (ref "C33") (pin "2") (pinfunction "2_2") (pintype "passive"))
      (node (ref "C34") (pin "1") (pinfunction "1_1") (pintype "passive"))
      (node (ref "C37") (pin "1") (pinfunction "1_1") (pintype "passive"))
      (node (ref "C38") (pin "1") (pinfunction "1_1") (pintype "passive"))
      (node (ref "C39") (pin "2") (pinfunction "2_2") (pintype "passive"))
      (node (ref "C4") (pin "2") (pinfunction "2_2") (pintype "passive"))
      (node (ref "C42") (pin "2") (pinfunction "2_2") (pintype "passive"))
      (node (ref "C43") (pin "2") (pinfunction "2_2") (pintype "passive"))
      (node (ref "C5") (pin "2") (pinfunction "2_2") (pintype "passive"))
      (node (ref "C6") (pin "2") (pinfunction "2_2") (pintype "passive"))
      (node (ref "C7") (pin "2") (pinfunction "2_2") (pintype "passive"))
      (node (ref "C8") (pin "2") (pinfunction "2_2") (pintype "passive"))
      (node (ref "C9") (pin "2") (pinfunction "2_2") (pintype "passive"))
      (node (ref "D3") (pin "2") (pinfunction "GND_2") (pintype "bidirectional"))
      (node (ref "D4") (pin "1") (pinfunction "K_1") (pintype "bidirectional"))
      (node (ref "EPD_C1") (pin "1") (pinfunction "1_1") (pintype "passive"))
      (node (ref "EPD_C10") (pin "1") (pinfunction "1_1") (pintype "passive"))
      (node (ref "EPD_C11") (pin "1") (pinfunction "1_1") (pintype "passive"))
      (node (ref "EPD_C12") (pin "1") (pinfunction "1_1") (pintype "passive"))
      (node (ref "EPD_C2") (pin "1") (pinfunction "1_1") (pintype "passive"))
      (node (ref "EPD_C5") (pin "1") (pinfunction "1_1") (pintype "passive"))
      (node (ref "EPD_C6") (pin "1") (pinfunction "1_1") (pintype "passive"))
      (node (ref "EPD_C7") (pin "1") (pinfunction "1_1") (pintype "passive"))
      (node (ref "EPD_C8") (pin "1") (pinfunction "1_1") (pintype "passive"))
      (node (ref "EPD_C9") (pin "1") (pinfunction "1_1") (pintype "passive"))
      (node (ref "IC1") (pin "D2") (pinfunction "GND_D2") (pintype "bidirectional"))
      (node (ref "IC2") (pin "B1") (pinfunction "IN/TRIG_B1") (pintype "bidirectional"))
      (node (ref "IC2") (pin "B3") (pinfunction "GND_B3") (pintype "bidirectional"))
      (node (ref "IC3") (pin "8") (pinfunction "GNDIO_8") (pintype "bidirectional"))
      (node (ref "IC3") (pin "9") (pinfunction "GND_9") (pintype "bidirectional"))
      (node (ref "IC9") (pin "B1") (pinfunction "VSEL_B1") (pintype "bidirectional"))
      (node (ref "IC9") (pin "C1") (pinfunction "AGND_C1") (pintype "bidirectional"))
      (node (ref "IC9") (pin "C2") (pinfunction "PGND_1_C2") (pintype "bidirectional"))
      (node (ref "IC9") (pin "C3") (pinfunction "PGND_2_C3") (pintype "bidirectional"))
      (node (ref "J1") (pin "17") (pinfunction "17_17") (pintype "bidirectional"))
      (node (ref "J1") (pin "8") (pinfunction "8_8") (pintype "bidirectional"))
      (node (ref "J1") (pin "MP1") (pinfunction "MP1_MP1") (pintype "bidirectional"))
      (node (ref "J1") (pin "MP2") (pinfunction "MP2_MP2") (pintype "bidirectional"))
      (node (ref "J2") (pin "3") (pinfunction "3_3") (pintype "bidirectional"))
      (node (ref "J2") (pin "5") (pinfunction "5_5") (pintype "bidirectional"))
      (node (ref "J4") (pin "A12_B1") (pinfunction "GND_A12_B1") (pintype "power_in"))
      (node (ref "J4") (pin "A1_B12") (pinfunction "GND_A1_B12") (pintype "power_in"))
      (node (ref "J4") (pin "SH1") (pinfunction "SHIELD_SH1") (pintype "passive"))
      (node (ref "J4") (pin "SH2") (pinfunction "SHIELD_SH2") (pintype "passive"))
      (node (ref "J4") (pin "SH3") (pinfunction "SHIELD_SH3") (pintype "passive"))
      (node (ref "J4") (pin "SH4") (pinfunction "SHIELD_SH4") (pintype "passive"))
      (node (ref "R1") (pin "1") (pinfunction "1_1") (pintype "bidirectional"))
      (node (ref "R1_USB") (pin "1") (pinfunction "1_1") (pintype "bidirectional"))
      (node (ref "R2_EP_DR") (pin "1") (pinfunction "1_1") (pintype "bidirectional"))
      (node (ref "R2_USB") (pin "2") (pinfunction "2_2") (pintype "bidirectional"))
      (node (ref "R3") (pin "1") (pinfunction "1_1") (pintype "bidirectional"))
      (node (ref "R_TYPE_SEL") (pin "1") (pinfunction "1_1") (pintype "bidirectional"))
      (node (ref "SJ1") (pin "1") (pinfunction "1_1") (pintype "passive"))
      (node (ref "SW_DN") (pin "1") (pinfunction "1_1") (pintype "passive"))
      (node (ref "SW_ENT") (pin "1") (pinfunction "1_1") (pintype "passive"))
      (node (ref "SW_UP") (pin "1") (pinfunction "1_1") (pintype "passive"))
      (node (ref "TP_BAT_GND") (pin "TP") (pinfunction "TP_TP") (pintype "input"))
      (node (ref "TP_GND") (pin "TP") (pinfunction "TP_TP") (pintype "input"))
      (node (ref "U1") (pin "P$74") (pinfunction "VSS_PAD_P$74") (pintype "bidirectional"))
      (node (ref "U1") (pin "P$75") (pinfunction "VSS_PAD_P$75") (pintype "bidirectional"))
      (node (ref "U1") (pin "P$76") (pinfunction "VSS_PAD_P$76") (pintype "bidirectional"))
      (node (ref "U1") (pin "P$77") (pinfunction "VSS_PAD_P$77") (pintype "bidirectional"))
      (node (ref "U1") (pin "P$78") (pinfunction "VSS_PAD_P$78") (pintype "bidirectional"))
      (node (ref "U1") (pin "P$79") (pinfunction "VSS_PAD_P$79") (pintype "bidirectional"))
      (node (ref "U1") (pin "P$80") (pinfunction "VSS_PAD_P$80") (pintype "bidirectional"))
      (node (ref "U1") (pin "P$81") (pinfunction "VSS_PAD_P$81") (pintype "bidirectional"))
      (node (ref "U1") (pin "P$82") (pinfunction "VSS_PAD_P$82") (pintype "bidirectional"))
      (node (ref "U1") (pin "P$83") (pinfunction "VSS_PAD_P$83") (pintype "bidirectional"))
      (node (ref "U1") (pin "P$84") (pinfunction "VSS_PAD_P$84") (pintype "bidirectional"))
      (node (ref "U1") (pin "P$85") (pinfunction "VSS_PAD_P$85") (pintype "bidirectional"))
      (node (ref "U1") (pin "P$86") (pinfunction "VSS_PAD_P$86") (pintype "bidirectional"))
      (node (ref "U1") (pin "P$87") (pinfunction "VSS_PAD_P$87") (pintype "bidirectional"))
      (node (ref "U1") (pin "P$88") (pinfunction "VSS_PAD_P$88") (pintype "bidirectional"))
      (node (ref "U1") (pin "P$89") (pinfunction "VSS_PAD_P$89") (pintype "bidirectional"))
      (node (ref "U1") (pin "P$90") (pinfunction "VSS_PAD_P$90") (pintype "bidirectional"))
      (node (ref "U1") (pin "P$B7") (pinfunction "VSS_P$B7") (pintype "power_in"))
      (node (ref "U1") (pin "P$F23") (pinfunction "VSS_PA_P$F23") (pintype "bidirectional"))
      (node (ref "U3") (pin "1") (pinfunction "CTG_1") (pintype "power_in"))
      (node (ref "U3") (pin "4") (pinfunction "GND_4") (pintype "power_in"))
      (node (ref "U3") (pin "6") (pinfunction "QSTRT_6") (pintype "input"))
      (node (ref "U3") (pin "9") (pinfunction "EP_9") (pintype "power_in"))
      (node (ref "X1") (pin "2") (pinfunction "2_2") (pintype "passive"))
      (node (ref "X1") (pin "4") (pinfunction "4_4") (pintype "passive"))
    )
    (net (code "22") (name "HAPTIC_EN{slash}1.4C") (class "Default")
      (node (ref "IC2") (pin "A1") (pinfunction "EN_A1") (pintype "bidirectional"))
    )
    (net (code "23") (name "HAPTIC_EN{slash}2.6A") (class "Default")
      (node (ref "U1") (pin "P$U1") (pinfunction "P0.12_P$U1") (pintype "bidirectional"))
    )
    (net (code "24") (name "IMU_INT1") (class "Default")
      (node (ref "IC3") (pin "5") (pinfunction "INT1_5") (pintype "bidirectional"))
      (node (ref "U1") (pin "P$N1") (pinfunction "P0.08_P$N1") (pintype "bidirectional"))
    )
    (net (code "25") (name "IMU_INT2") (class "Default")
      (node (ref "IC3") (pin "6") (pinfunction "INT2_6") (pintype "bidirectional"))
      (node (ref "U1") (pin "P$P2") (pinfunction "P1.08_P$P2") (pintype "bidirectional"))
    )
    (net (code "26") (name "LX1") (class "Default")
      (node (ref "IC9") (pin "B2") (pinfunction "SW1_1_B2") (pintype "bidirectional"))
      (node (ref "IC9") (pin "B3") (pinfunction "SW1_2_B3") (pintype "bidirectional"))
      (node (ref "L7") (pin "1") (pinfunction "1_1") (pintype "bidirectional"))
    )
    (net (code "27") (name "LX2") (class "Default")
      (node (ref "IC9") (pin "D2") (pinfunction "SW2_1_D2") (pintype "bidirectional"))
      (node (ref "IC9") (pin "D3") (pinfunction "SW2_2_D3") (pintype "bidirectional"))
      (node (ref "L7") (pin "2") (pinfunction "2_2") (pintype "bidirectional"))
    )
    (net (code "28") (name "MOSI{slash}1.5B") (class "Default")
      (node (ref "J1") (pin "14") (pinfunction "14_14") (pintype "bidirectional"))
    )
    (net (code "29") (name "MOSI{slash}2.2D") (class "Default")
      (node (ref "U1") (pin "P$B13") (pinfunction "P0.03/AIN1_P$B13") (pintype "bidirectional"))
    )
    (net (code "30") (name "N$1") (class "Default")
      (node (ref "C8") (pin "1") (pinfunction "1_1") (pintype "passive"))
      (node (ref "U1") (pin "P$AD23") (pinfunction "VDD_P$AD23") (pintype "power_in"))
    )
    (net (code "31") (name "Net-(ANT1-FEED)") (class "Default")
      (node (ref "ANT1") (pin "1") (pinfunction "FEED_1") (pintype "input"))
      (node (ref "C22") (pin "1") (pinfunction "1_1") (pintype "passive"))
      (node (ref "C4") (pin "1") (pinfunction "1_1") (pintype "passive"))
      (node (ref "L1") (pin "2") (pinfunction "2_2") (pintype "passive"))
    )
    (net (code "32") (name "Net-(C14-Pad1)") (class "Default")
      (node (ref "C14") (pin "1") (pinfunction "1_1") (pintype "passive"))
      (node (ref "U1") (pin "P$B1") (pinfunction "VDD_P$B1") (pintype "power_in"))
    )
    (net (code "33") (name "Net-(D2-K)") (class "Default")
      (node (ref "D2") (pin "1") (pinfunction "K_1") (pintype "bidirectional"))
      (node (ref "D4") (pin "2") (pinfunction "A_2") (pintype "bidirectional"))
      (node (ref "U$4") (pin "1") (pinfunction "1_1") (pintype "passive"))
    )
    (net (code "34") (name "Net-(D5-A)") (class "Default")
      (node (ref "D5") (pin "2") (pinfunction "A_2") (pintype "bidirectional"))
      (node (ref "L5") (pin "1") (pinfunction "1_1") (pintype "passive"))
      (node (ref "Q3") (pin "3") (pinfunction "D_3") (pintype "bidirectional"))
      (node (ref "U$4") (pin "2") (pinfunction "2_2") (pintype "passive"))
    )
    (net (code "35") (name "Net-(EPD_C1-Pad2)") (class "Default")
      (node (ref "EPD_C1") (pin "2") (pinfunction "2_2") (pintype "passive"))
      (node (ref "J1") (pin "5") (pinfunction "5_5") (pintype "bidirectional"))
    )
    (net (code "36") (name "Net-(EPD_C2-Pad2)") (class "Default")
      (node (ref "EPD_C2") (pin "2") (pinfunction "2_2") (pintype "passive"))
      (node (ref "J1") (pin "4") (pinfunction "4_4") (pintype "bidirectional"))
    )
    (net (code "37") (name "Net-(EPD_C5-Pad2)") (class "Default")
      (node (ref "EPD_C5") (pin "2") (pinfunction "2_2") (pintype "passive"))
      (node (ref "J1") (pin "15") (pinfunction "15_15") (pintype "bidirectional"))
      (node (ref "J1") (pin "16") (pinfunction "16_16") (pintype "bidirectional"))
    )
    (net (code "38") (name "Net-(EPD_C6-Pad2)") (class "Default")
      (node (ref "EPD_C6") (pin "2") (pinfunction "2_2") (pintype "passive"))
      (node (ref "J1") (pin "18") (pinfunction "18_18") (pintype "bidirectional"))
    )
    (net (code "39") (name "Net-(EPD_C7-Pad2)") (class "Default")
      (node (ref "EPD_C7") (pin "2") (pinfunction "2_2") (pintype "passive"))
      (node (ref "J1") (pin "19") (pinfunction "19_19") (pintype "bidirectional"))
    )
    (net (code "40") (name "Net-(EPD_C8-Pad2)") (class "Default")
      (node (ref "EPD_C8") (pin "2") (pinfunction "2_2") (pintype "passive"))
      (node (ref "J1") (pin "20") (pinfunction "20_20") (pintype "bidirectional"))
    )
    (net (code "41") (name "Net-(EPD_C9-Pad2)") (class "Default")
      (node (ref "EPD_C9") (pin "2") (pinfunction "2_2") (pintype "passive"))
      (node (ref "J1") (pin "21") (pinfunction "21_21") (pintype "bidirectional"))
    )
    (net (code "42") (name "Net-(EPD_C12-Pad2)") (class "Default")
      (node (ref "EPD_C12") (pin "2") (pinfunction "2_2") (pintype "passive"))
      (node (ref "J1") (pin "24") (pinfunction "24_24") (pintype "bidirectional"))
    )
    (net (code "43") (name "Net-(IC1-TS{slash}MR)") (class "Default")
      (node (ref "IC1") (pin "D1") (pinfunction "TS/MR_D1") (pintype "bidirectional"))
      (node (ref "R1") (pin "2") (pinfunction "2_2") (pintype "bidirectional"))
    )
    (net (code "44") (name "Net-(IC2-REG)") (class "Default")
      (node (ref "C32") (pin "2") (pinfunction "2_2") (pintype "passive"))
      (node (ref "IC2") (pin "A2") (pinfunction "REG_A2") (pintype "bidirectional"))
    )
    (net (code "45") (name "Net-(IC3-SDO)") (class "Default")
      (node (ref "IC3") (pin "1") (pinfunction "SDO_1") (pintype "bidirectional"))
      (node (ref "R3") (pin "2") (pinfunction "2_2") (pintype "bidirectional"))
    )
    (net (code "46") (name "Net-(IC9-SCL)") (class "Default")
      (node (ref "IC9") (pin "D1") (pinfunction "SCL_D1") (pintype "bidirectional"))
      (node (ref "R4") (pin "2") (pinfunction "2_2") (pintype "bidirectional"))
    )
    (net (code "47") (name "Net-(IC9-SDA)") (class "Default")
      (node (ref "IC9") (pin "E1") (pinfunction "SDA_E1") (pintype "bidirectional"))
      (node (ref "R2") (pin "2") (pinfunction "2_2") (pintype "bidirectional"))
    )
    (net (code "48") (name "Net-(J4-CC1)") (class "Default")
      (node (ref "J4") (pin "A5") (pinfunction "CC1_A5") (pintype "bidirectional"))
      (node (ref "R1_USB") (pin "2") (pinfunction "2_2") (pintype "bidirectional"))
    )
    (net (code "49") (name "Net-(J4-CC2)") (class "Default")
      (node (ref "J4") (pin "B5") (pinfunction "CC2_B5") (pintype "bidirectional"))
      (node (ref "R2_USB") (pin "1") (pinfunction "1_1") (pintype "bidirectional"))
    )
    (net (code "50") (name "Net-(L2-Pad2)") (class "Default")
      (node (ref "L2") (pin "2") (pinfunction "2_2") (pintype "passive"))
      (node (ref "L3") (pin "1") (pinfunction "1_1") (pintype "passive"))
    )
    (net (code "51") (name "Net-(R1_EP_DR-Pad1)") (class "Default")
      (node (ref "R1_EP_DR") (pin "1") (pinfunction "1_1") (pintype "bidirectional"))
      (node (ref "R_TYPE_SEL") (pin "2") (pinfunction "2_2") (pintype "bidirectional"))
      (node (ref "SJ1") (pin "2") (pinfunction "2_2") (pintype "passive"))
    )
    (net (code "52") (name "Net-(U1-ANT)") (class "Default")
      (node (ref "C3") (pin "1") (pinfunction "1_1") (pintype "passive"))
      (node (ref "L1") (pin "1") (pinfunction "1_1") (pintype "passive"))
      (node (ref "U1") (pin "P$H23") (pinfunction "ANT_P$H23") (pintype "bidirectional"))
    )
    (net (code "53") (name "Net-(U1-DCC)") (class "Default")
      (node (ref "L2") (pin "1") (pinfunction "1_1") (pintype "passive"))
      (node (ref "U1") (pin "P$B3") (pinfunction "DCC_P$B3") (pintype "output"))
    )
    (net (code "54") (name "Net-(U1-DEC1)") (class "Default")
      (node (ref "C5") (pin "1") (pinfunction "1_1") (pintype "passive"))
      (node (ref "U1") (pin "P$C1") (pinfunction "DEC1_P$C1") (pintype "power_in"))
    )
    (net (code "55") (name "Net-(U1-DEC2)") (class "Default")
      (node (ref "C13") (pin "1") (pinfunction "1_1") (pintype "passive"))
      (node (ref "U1") (pin "P$A18") (pinfunction "DEC2_P$A18") (pintype "bidirectional"))
    )
    (net (code "56") (name "Net-(U1-DEC3)") (class "Default")
      (node (ref "C11") (pin "1") (pinfunction "1_1") (pintype "passive"))
      (node (ref "U1") (pin "P$D23") (pinfunction "DEC3_P$D23") (pintype "bidirectional"))
    )
    (net (code "57") (name "Net-(U1-DEC3V3)") (class "Default")
      (node (ref "C20") (pin "1") (pinfunction "1_1") (pintype "passive"))
      (node (ref "U1") (pin "P$AC5") (pinfunction "DEC3V3_P$AC5") (pintype "bidirectional"))
    )
    (net (code "58") (name "Net-(U1-DEC4)") (class "Default")
      (node (ref "C10") (pin "1") (pinfunction "1_1") (pintype "passive"))
      (node (ref "C15") (pin "1") (pinfunction "1_1") (pintype "passive"))
      (node (ref "C16") (pin "1") (pinfunction "1_1") (pintype "passive"))
      (node (ref "L3") (pin "2") (pinfunction "2_2") (pintype "passive"))
      (node (ref "U1") (pin "P$B5") (pinfunction "DEC4_P$B5") (pintype "power_in"))
      (node (ref "U1") (pin "P$E24") (pinfunction "DEC6_P$E24") (pintype "bidirectional"))
    )
    (net (code "59") (name "Net-(U1-DEC5)") (class "Default")
      (node (ref "C9") (pin "1") (pinfunction "1_1") (pintype "passive"))
      (node (ref "U1") (pin "P$N24") (pinfunction "DEC5_P$N24") (pintype "bidirectional"))
    )
    (net (code "60") (name "Net-(U1-P0.00{slash}XL1)") (class "Default")
      (node (ref "C17") (pin "2") (pinfunction "2_2") (pintype "passive"))
      (node (ref "U1") (pin "P$D2") (pinfunction "P0.00/XL1_P$D2") (pintype "bidirectional"))
      (node (ref "X2") (pin "2") (pinfunction "2_2") (pintype "passive"))
    )
    (net (code "61") (name "Net-(U1-P0.01{slash}XL2)") (class "Default")
      (node (ref "C18") (pin "2") (pinfunction "2_2") (pintype "passive"))
      (node (ref "U1") (pin "P$F2") (pinfunction "P0.01/XL2_P$F2") (pintype "bidirectional"))
      (node (ref "X2") (pin "1") (pinfunction "1_1") (pintype "passive"))
    )
    (net (code "62") (name "Net-(U1-XC1)") (class "Default")
      (node (ref "C1") (pin "1") (pinfunction "1_1") (pintype "passive"))
      (node (ref "U1") (pin "P$B24") (pinfunction "XC1_P$B24") (pintype "input"))
      (node (ref "X1") (pin "1") (pinfunction "1_1") (pintype "passive"))
    )
    (net (code "63") (name "Net-(U1-XC2)") (class "Default")
      (node (ref "C2") (pin "1") (pinfunction "1_1") (pintype "passive"))
      (node (ref "U1") (pin "P$A23") (pinfunction "XC2_P$A23") (pintype "output"))
      (node (ref "X1") (pin "3") (pinfunction "3_3") (pintype "passive"))
    )
    (net (code "64") (name "OUT+") (class "Default")
      (node (ref "IC2") (pin "A3") (pinfunction "OUT+_A3") (pintype "bidirectional"))
      (node (ref "TP_OP") (pin "TP") (pinfunction "TP_TP") (pintype "input"))
    )
    (net (code "65") (name "OUT-") (class "Default")
      (node (ref "IC2") (pin "C3") (pinfunction "OUT-_C3") (pintype "bidirectional"))
      (node (ref "TP_ON") (pin "TP") (pinfunction "TP_TP") (pintype "input"))
    )
    (net (code "66") (name "P0.04") (class "Default")
      (node (ref "U1") (pin "P$J1") (pinfunction "P0.04/AIN2_P$J1") (pintype "bidirectional"))
    )
    (net (code "67") (name "P0.09") (class "Default")
      (node (ref "U1") (pin "P$L24") (pinfunction "P0.09/NFC1_P$L24") (pintype "bidirectional"))
    )
    (net (code "68") (name "P0.13{slash}1.5D") (class "Default")
      (node (ref "C30") (pin "2") (pinfunction "2_2") (pintype "passive"))
      (node (ref "R5") (pin "1") (pinfunction "1_1") (pintype "bidirectional"))
      (node (ref "SW_UP") (pin "2") (pinfunction "2_2") (pintype "passive"))
    )
    (net (code "69") (name "P0.13{slash}2.6C") (class "Default")
      (node (ref "U1") (pin "P$AD8") (pinfunction "P0.13_P$AD8") (pintype "bidirectional"))
    )
    (net (code "70") (name "P0.14{slash}1.5D") (class "Default")
      (node (ref "C31") (pin "2") (pinfunction "2_2") (pintype "passive"))
      (node (ref "R8") (pin "1") (pinfunction "1_1") (pintype "bidirectional"))
      (node (ref "SW_ENT") (pin "2") (pinfunction "2_2") (pintype "passive"))
    )
    (net (code "71") (name "P0.14{slash}2.7C") (class "Default")
      (node (ref "U1") (pin "P$AC9") (pinfunction "P0.14_P$AC9") (pintype "bidirectional"))
    )
    (net (code "72") (name "P0.15{slash}1.5D") (class "Default")
      (node (ref "C29\\") (pin "2") (pinfunction "2_2") (pintype "passive"))
      (node (ref "R7") (pin "1") (pinfunction "1_1") (pintype "bidirectional"))
      (node (ref "SW_DN") (pin "2") (pinfunction "2_2") (pintype "passive"))
    )
    (net (code "73") (name "P0.19") (class "Default")
      (node (ref "U1") (pin "P$AC15") (pinfunction "P0.19_P$AC15") (pintype "bidirectional"))
    )
    (net (code "74") (name "P0.20") (class "Default")
      (node (ref "U1") (pin "P$AD16") (pinfunction "P0.20_P$AD16") (pintype "bidirectional"))
    )
    (net (code "75") (name "P0.21") (class "Default")
      (node (ref "U1") (pin "P$AC17") (pinfunction "P0.21_P$AC17") (pintype "bidirectional"))
    )
    (net (code "76") (name "P0.22") (class "Default")
      (node (ref "U1") (pin "P$AD18") (pinfunction "P0.22_P$AD18") (pintype "bidirectional"))
    )
    (net (code "77") (name "P0.23") (class "Default")
      (node (ref "U1") (pin "P$AC19") (pinfunction "P0.23_P$AC19") (pintype "bidirectional"))
    )
    (net (code "78") (name "P0.24") (class "Default")
      (node (ref "U1") (pin "P$AD20") (pinfunction "P0.24_P$AD20") (pintype "bidirectional"))
    )
    (net (code "79") (name "P0.25") (class "Default")
      (node (ref "U1") (pin "P$AC21") (pinfunction "P0.25_P$AC21") (pintype "bidirectional"))
    )
    (net (code "80") (name "P0.26") (class "Default")
      (node (ref "U1") (pin "P$G1") (pinfunction "P0.26_P$G1") (pintype "bidirectional"))
    )
    (net (code "81") (name "P0.27") (class "Default")
      (node (ref "U1") (pin "P$H2") (pinfunction "P0.27_P$H2") (pintype "bidirectional"))
    )
    (net (code "82") (name "P0.28") (class "Default")
      (node (ref "U1") (pin "P$B11") (pinfunction "P0.28/AIN4_P$B11") (pintype "bidirectional"))
    )
    (net (code "83") (name "P0.29") (class "Default")
      (node (ref "U1") (pin "P$A10") (pinfunction "P0.29/AIN5_P$A10") (pintype "bidirectional"))
    )
    (net (code "84") (name "P0.30") (class "Default")
      (node (ref "U1") (pin "P$B9") (pinfunction "P0.30/AIN6_P$B9") (pintype "bidirectional"))
    )
    (net (code "85") (name "P0.31") (class "Default")
      (node (ref "U1") (pin "P$A8") (pinfunction "P0.31/AIN7_P$A8") (pintype "bidirectional"))
    )
    (net (code "86") (name "P1.01{slash}1.6C") (class "Default")
      (node (ref "Q1") (pin "1") (pinfunction "G_1") (pintype "bidirectional"))
      (node (ref "R_PWR_EPD") (pin "1") (pinfunction "1_1") (pintype "bidirectional"))
    )
    (net (code "87") (name "P1.01{slash}2.4B") (class "Default")
      (node (ref "U1") (pin "P$Y23") (pinfunction "P1.01_P$Y23") (pintype "bidirectional"))
    )
    (net (code "88") (name "P1.02{slash}2.8C") (class "Default")
      (node (ref "U1") (pin "P$W24") (pinfunction "P1.02_P$W24") (pintype "bidirectional"))
    )
    (net (code "89") (name "P1.03") (class "Default")
      (node (ref "U1") (pin "P$V23") (pinfunction "P1.03_P$V23") (pintype "bidirectional"))
    )
    (net (code "90") (name "P1.04") (class "Default")
      (node (ref "U1") (pin "P$U24") (pinfunction "P1.04_P$U24") (pintype "bidirectional"))
    )
    (net (code "91") (name "P1.05") (class "Default")
      (node (ref "U1") (pin "P$T23") (pinfunction "P1.05_P$T23") (pintype "bidirectional"))
    )
    (net (code "92") (name "P1.06") (class "Default")
      (node (ref "U1") (pin "P$R24") (pinfunction "P1.06_P$R24") (pintype "bidirectional"))
    )
    (net (code "93") (name "P1.07") (class "Default")
      (node (ref "U1") (pin "P$P23") (pinfunction "P1.07_P$P23") (pintype "bidirectional"))
    )
    (net (code "94") (name "P1.09") (class "Default")
      (node (ref "U1") (pin "P$R1") (pinfunction "P1.09_P$R1") (pintype "bidirectional"))
    )
    (net (code "95") (name "P1.10") (class "Default")
      (node (ref "U1") (pin "P$A20") (pinfunction "P1.10_P$A20") (pintype "bidirectional"))
    )
    (net (code "96") (name "P1.11") (class "Default")
      (node (ref "U1") (pin "P$B19") (pinfunction "P1.11_P$B19") (pintype "bidirectional"))
    )
    (net (code "97") (name "P1.12") (class "Default")
      (node (ref "U1") (pin "P$B17") (pinfunction "P1.12_P$B17") (pintype "bidirectional"))
    )
    (net (code "98") (name "P1.13") (class "Default")
      (node (ref "U1") (pin "P$A16") (pinfunction "P1.13_P$A16") (pintype "bidirectional"))
    )
    (net (code "99") (name "P1.14") (class "Default")
      (node (ref "U1") (pin "P$B15") (pinfunction "P1.14_P$B15") (pintype "bidirectional"))
    )
    (net (code "100") (name "P1.15") (class "Default")
      (node (ref "U1") (pin "P$A14") (pinfunction "P1.15_P$A14") (pintype "bidirectional"))
    )
    (net (code "101") (name "PMIC_INT") (class "Default")
      (node (ref "IC1") (pin "A1") (pinfunction "~{INT}_A1") (pintype "bidirectional"))
      (node (ref "U1") (pin "P$T2") (pinfunction "P0.11_P$T2") (pintype "bidirectional"))
    )
    (net (code "102") (name "PREVGH") (class "Default")
      (node (ref "D5") (pin "1") (pinfunction "K_1") (pintype "bidirectional"))
      (node (ref "EPD_C10") (pin "2") (pinfunction "2_2") (pintype "passive"))
      (node (ref "J1") (pin "22") (pinfunction "22_22") (pintype "bidirectional"))
    )
    (net (code "103") (name "PREVGL") (class "Default")
      (node (ref "D2") (pin "2") (pinfunction "A_2") (pintype "bidirectional"))
      (node (ref "EPD_C11") (pin "2") (pinfunction "2_2") (pintype "passive"))
      (node (ref "J1") (pin "23") (pinfunction "23_23") (pintype "bidirectional"))
    )
    (net (code "104") (name "RESE") (class "Default")
      (node (ref "J1") (pin "3") (pinfunction "3_3") (pintype "bidirectional"))
      (node (ref "Q3") (pin "2") (pinfunction "S_2") (pintype "bidirectional"))
      (node (ref "R1_EP_DR") (pin "2") (pinfunction "2_2") (pintype "bidirectional"))
    )
    (net (code "105") (name "RESET") (class "Default")
      (node (ref "J2") (pin "6") (pinfunction "6_6") (pintype "bidirectional"))
      (node (ref "TP_RESET") (pin "TP") (pinfunction "TP_TP") (pintype "input"))
      (node (ref "U1") (pin "P$AC13") (pinfunction "P0.18/RESET_P$AC13") (pintype "bidirectional"))
    )
    (net (code "106") (name "SCK{slash}1.5B") (class "Default")
      (node (ref "J1") (pin "13") (pinfunction "13_13") (pintype "bidirectional"))
    )
    (net (code "107") (name "SCK{slash}2.2D") (class "Default")
      (node (ref "U1") (pin "P$A12") (pinfunction "P0.02/AIN0_P$A12") (pintype "bidirectional"))
    )
    (net (code "108") (name "SCL{slash}1.4C") (class "Default")
      (node (ref "IC2") (pin "C1") (pinfunction "SCL_C1") (pintype "bidirectional"))
      (node (ref "U3") (pin "7") (pinfunction "SCL_7") (pintype "input"))
    )
    (net (code "109") (name "SCL{slash}2.4C") (class "Default")
      (node (ref "IC1") (pin "B1") (pinfunction "SCL_B1") (pintype "bidirectional"))
      (node (ref "IC3") (pin "12") (pinfunction "SCX_12") (pintype "bidirectional"))
      (node (ref "R17") (pin "2") (pinfunction "2_2") (pintype "bidirectional"))
      (node (ref "R4") (pin "1") (pinfunction "1_1") (pintype "bidirectional"))
      (node (ref "TP_SCL") (pin "TP") (pinfunction "TP_TP") (pintype "input"))
      (node (ref "U1") (pin "P$M2") (pinfunction "P0.07_P$M2") (pintype "bidirectional"))
    )
    (net (code "110") (name "SDA{slash}1.4C") (class "Default")
      (node (ref "IC2") (pin "B2") (pinfunction "SDA_B2") (pintype "bidirectional"))
      (node (ref "U3") (pin "8") (pinfunction "SDA_8") (pintype "bidirectional"))
    )
    (net (code "111") (name "SDA{slash}2.4C") (class "Default")
      (node (ref "IC1") (pin "C1") (pinfunction "SDA_C1") (pintype "bidirectional"))
      (node (ref "IC3") (pin "2") (pinfunction "SDX_2") (pintype "bidirectional"))
      (node (ref "R18") (pin "2") (pinfunction "2_2") (pintype "bidirectional"))
      (node (ref "R2") (pin "1") (pinfunction "1_1") (pintype "bidirectional"))
      (node (ref "TP_SDA") (pin "TP") (pinfunction "TP_TP") (pintype "input"))
      (node (ref "U1") (pin "P$L1") (pinfunction "P0.06_P$L1") (pintype "bidirectional"))
    )
    (net (code "112") (name "SWDCLK") (class "Default")
      (node (ref "J2") (pin "4") (pinfunction "4_4") (pintype "bidirectional"))
      (node (ref "TP_SWDCLK") (pin "TP") (pinfunction "TP_TP") (pintype "input"))
      (node (ref "U1") (pin "P$AA24") (pinfunction "SWDCLK_P$AA24") (pintype "input"))
    )
    (net (code "113") (name "SWDIO") (class "Default")
      (node (ref "J2") (pin "2") (pinfunction "2_2") (pintype "bidirectional"))
      (node (ref "TP_SWDIO") (pin "TP") (pinfunction "TP_TP") (pintype "input"))
      (node (ref "U1") (pin "P$AC24") (pinfunction "SWDIO_P$AC24") (pintype "bidirectional"))
    )
    (net (code "114") (name "SWO") (class "Default")
      (node (ref "TP_SWO") (pin "TP") (pinfunction "TP_TP") (pintype "input"))
      (node (ref "U1") (pin "P$AD22") (pinfunction "P1.00_P$AD22") (pintype "bidirectional"))
    )
    (net (code "115") (name "VBAT{slash}1.2A") (class "Default")
      (node (ref "C27") (pin "2") (pinfunction "2_2") (pintype "passive"))
      (node (ref "TP_VBAT") (pin "TP") (pinfunction "TP_TP") (pintype "input"))
      (node (ref "U3") (pin "2") (pinfunction "CELL_2") (pintype "power_in"))
      (node (ref "U3") (pin "3") (pinfunction "VDD_3") (pintype "power_in"))
    )
    (net (code "116") (name "VBAT{slash}2.5C") (class "Default")
      (node (ref "C37") (pin "2") (pinfunction "2_2") (pintype "passive"))
      (node (ref "IC1") (pin "C2") (pinfunction "BAT_C2") (pintype "bidirectional"))
    )
    (net (code "117") (name "VBUS{slash}1.5D") (class "Default")
      (node (ref "C42") (pin "1") (pinfunction "1_1") (pintype "passive"))
      (node (ref "C43") (pin "1") (pinfunction "1_1") (pintype "passive"))
      (node (ref "D3") (pin "5") (pinfunction "VBUS_5") (pintype "bidirectional"))
      (node (ref "J4") (pin "A4_B9") (pinfunction "VBUS_A4_B9") (pintype "power_in"))
      (node (ref "J4") (pin "A9_B4") (pinfunction "VBUS_A9_B4") (pintype "power_in"))
    )
    (net (code "118") (name "VBUS{slash}2.6D") (class "Default")
      (node (ref "C21") (pin "1") (pinfunction "1_1") (pintype "passive"))
      (node (ref "C38") (pin "2") (pinfunction "2_2") (pintype "passive"))
      (node (ref "IC1") (pin "A2") (pinfunction "IN_A2") (pintype "bidirectional"))
      (node (ref "U1") (pin "P$AD2") (pinfunction "VBUS_P$AD2") (pintype "power_in"))
    )
    (net (code "119") (name "VREG") (class "Default")
      (node (ref "C23") (pin "1") (pinfunction "1_1") (pintype "passive"))
      (node (ref "C24") (pin "2") (pinfunction "2_2") (pintype "passive"))
      (node (ref "C39") (pin "1") (pinfunction "1_1") (pintype "passive"))
      (node (ref "IC1") (pin "B2") (pinfunction "SYS_B2") (pintype "bidirectional"))
      (node (ref "IC9") (pin "A1") (pinfunction "EN_A1") (pintype "bidirectional"))
      (node (ref "IC9") (pin "A2") (pinfunction "VIN_1_A2") (pintype "bidirectional"))
      (node (ref "IC9") (pin "A3") (pinfunction "VIN_2_A3") (pintype "bidirectional"))
      (node (ref "TP_VREG") (pin "TP") (pinfunction "TP_TP") (pintype "input"))
    )
    (net (code "120") (name "unconnected-(ANT1-NC-Pad2)") (class "Default")
      (node (ref "ANT1") (pin "2") (pinfunction "NC_2") (pintype "no_connect"))
    )
    (net (code "121") (name "unconnected-(IC3-ASCL-Pad11)") (class "Default")
      (node (ref "IC3") (pin "11") (pinfunction "ASCL_11") (pintype "bidirectional"))
    )
    (net (code "122") (name "unconnected-(IC3-ASDA-Pad4)") (class "Default")
      (node (ref "IC3") (pin "4") (pinfunction "ASDA_4") (pintype "bidirectional"))
    )
    (net (code "123") (name "unconnected-(J1-Pad1)") (class "Default")
      (node (ref "J1") (pin "1") (pinfunction "1_1") (pintype "bidirectional"))
    )
    (net (code "124") (name "unconnected-(J1-Pad6)") (class "Default")
      (node (ref "J1") (pin "6") (pinfunction "6_6") (pintype "bidirectional"))
    )
    (net (code "125") (name "unconnected-(J1-Pad7)") (class "Default")
      (node (ref "J1") (pin "7") (pinfunction "7_7") (pintype "bidirectional"))
    )
    (net (code "126") (name "unconnected-(J4-SBU1-PadA8)") (class "Default")
      (node (ref "J4") (pin "A8") (pinfunction "SBU1_A8") (pintype "bidirectional"))
    )
    (net (code "127") (name "unconnected-(J4-SBU2-PadB8)") (class "Default")
      (node (ref "J4") (pin "B8") (pinfunction "SBU2_B8") (pintype "bidirectional"))
    )
    (net (code "128") (name "unconnected-(U1-DCCH-PadP$AB2)") (class "Default")
      (node (ref "U1") (pin "P$AB2") (pinfunction "DCCH_P$AB2") (pintype "bidirectional"))
    )
  )
)
